# Controller_v_2.net
KiCad netlist of a schematic drawn in EAGLE
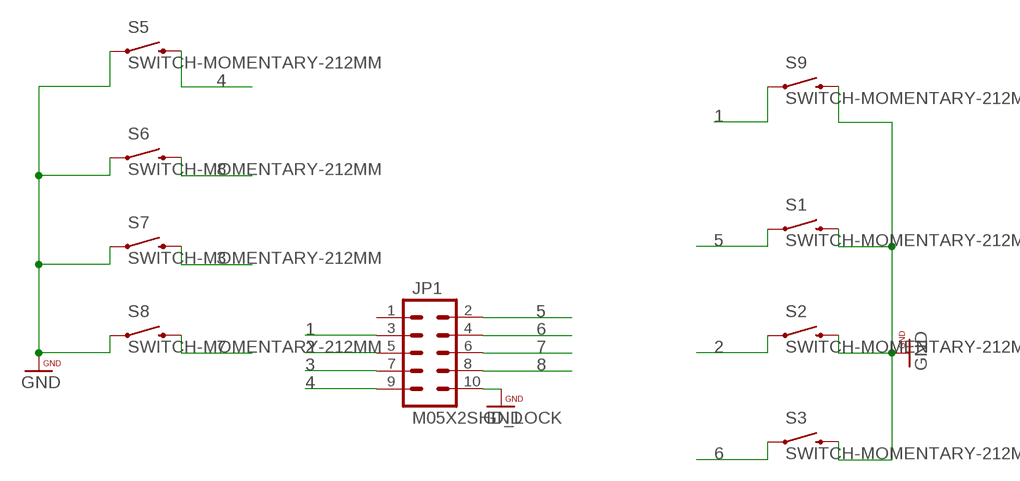
[diagram p0: schematic, sheet 1]

(export (version "E")
  (design (tool "Eeschema 10.0.6"))
  (components
    (comp (ref "JP1")
      (value "M05X2SHD_LOCK")
      (footprint "eagle-import:2X5-SHROUDED_LOCK")
      (libsource (lib "eagle-import") (part "M05X2SHD_LOCK"))
    )
    (comp (ref "S1")
      (value "SWITCH-MOMENTARY-212MM")
      (footprint "eagle-import:TACTILE-PTH-12MM")
      (libsource (lib "eagle-import") (part "SWITCH-MOMENTARY-212MM"))
    )
    (comp (ref "S2")
      (value "SWITCH-MOMENTARY-212MM")
      (footprint "eagle-import:TACTILE-PTH-12MM")
      (libsource (lib "eagle-import") (part "SWITCH-MOMENTARY-212MM"))
    )
    (comp (ref "S3")
      (value "SWITCH-MOMENTARY-212MM")
      (footprint "eagle-import:TACTILE-PTH-12MM")
      (libsource (lib "eagle-import") (part "SWITCH-MOMENTARY-212MM"))
    )
    (comp (ref "S5")
      (value "SWITCH-MOMENTARY-212MM")
      (footprint "eagle-import:TACTILE-PTH-12MM")
      (libsource (lib "eagle-import") (part "SWITCH-MOMENTARY-212MM"))
    )
    (comp (ref "S6")
      (value "SWITCH-MOMENTARY-212MM")
      (footprint "eagle-import:TACTILE-PTH-12MM")
      (libsource (lib "eagle-import") (part "SWITCH-MOMENTARY-212MM"))
    )
    (comp (ref "S7")
      (value "SWITCH-MOMENTARY-212MM")
      (footprint "eagle-import:TACTILE-PTH-12MM")
      (libsource (lib "eagle-import") (part "SWITCH-MOMENTARY-212MM"))
    )
    (comp (ref "S8")
      (value "SWITCH-MOMENTARY-212MM")
      (footprint "eagle-import:TACTILE-PTH-12MM")
      (libsource (lib "eagle-import") (part "SWITCH-MOMENTARY-212MM"))
    )
    (comp (ref "S9")
      (value "SWITCH-MOMENTARY-212MM")
      (footprint "eagle-import:TACTILE-PTH-12MM")
      (libsource (lib "eagle-import") (part "SWITCH-MOMENTARY-212MM"))
    )
  )
  (nets
    (net (code "1") (name "/1") (class "Default")
      (node (ref "JP1") (pin "3") (pinfunction "3_3") (pintype "passive"))
      (node (ref "S9") (pin "1") (pinfunction "1_1") (pintype "passive"))
    )
    (net (code "2") (name "/2") (class "Default")
      (node (ref "JP1") (pin "5") (pinfunction "5_5") (pintype "passive"))
      (node (ref "S2") (pin "1") (pinfunction "1_1") (pintype "passive"))
    )
    (net (code "3") (name "/3") (class "Default")
      (node (ref "JP1") (pin "7") (pinfunction "7_7") (pintype "passive"))
      (node (ref "S7") (pin "3") (pinfunction "2_3") (pintype "passive"))
    )
    (net (code "4") (name "/4") (class "Default")
      (node (ref "JP1") (pin "9") (pinfunction "9_9") (pintype "passive"))
      (node (ref "S5") (pin "3") (pinfunction "2_3") (pintype "passive"))
    )
    (net (code "5") (name "/5") (class "Default")
      (node (ref "JP1") (pin "2") (pinfunction "2_2") (pintype "passive"))
      (node (ref "S1") (pin "1") (pinfunction "1_1") (pintype "passive"))
    )
    (net (code "6") (name "/6") (class "Default")
      (node (ref "JP1") (pin "4") (pinfunction "4_4") (pintype "passive"))
      (node (ref "S3") (pin "1") (pinfunction "1_1") (pintype "passive"))
    )
    (net (code "7") (name "/7") (class "Default")
      (node (ref "JP1") (pin "6") (pinfunction "6_6") (pintype "passive"))
      (node (ref "S8") (pin "3") (pinfunction "2_3") (pintype "passive"))
    )
    (net (code "8") (name "/8") (class "Default")
      (node (ref "JP1") (pin "8") (pinfunction "8_8") (pintype "passive"))
      (node (ref "S6") (pin "3") (pinfunction "2_3") (pintype "passive"))
    )
    (net (code "9") (name "GND") (class "Default")
      (node (ref "JP1") (pin "10") (pinfunction "10_10") (pintype "passive"))
      (node (ref "S1") (pin "3") (pinfunction "2_3") (pintype "passive"))
      (node (ref "S2") (pin "3") (pinfunction "2_3") (pintype "passive"))
      (node (ref "S3") (pin "3") (pinfunction "2_3") (pintype "passive"))
      (node (ref "S5") (pin "1") (pinfunction "1_1") (pintype "passive"))
      (node (ref "S6") (pin "1") (pinfunction "1_1") (pintype "passive"))
      (node (ref "S7") (pin "1") (pinfunction "1_1") (pintype "passive"))
      (node (ref "S8") (pin "1") (pinfunction "1_1") (pintype "passive"))
      (node (ref "S9") (pin "3") (pinfunction "2_3") (pintype "passive"))
    )
    (net (code "10") (name "unconnected-(JP1-Pad1)") (class "Default")
      (node (ref "JP1") (pin "1") (pinfunction "1_1") (pintype "passive"))
    )
  )
)
